# Power.net
KiCad netlist of a schematic drawn in Altium Designer
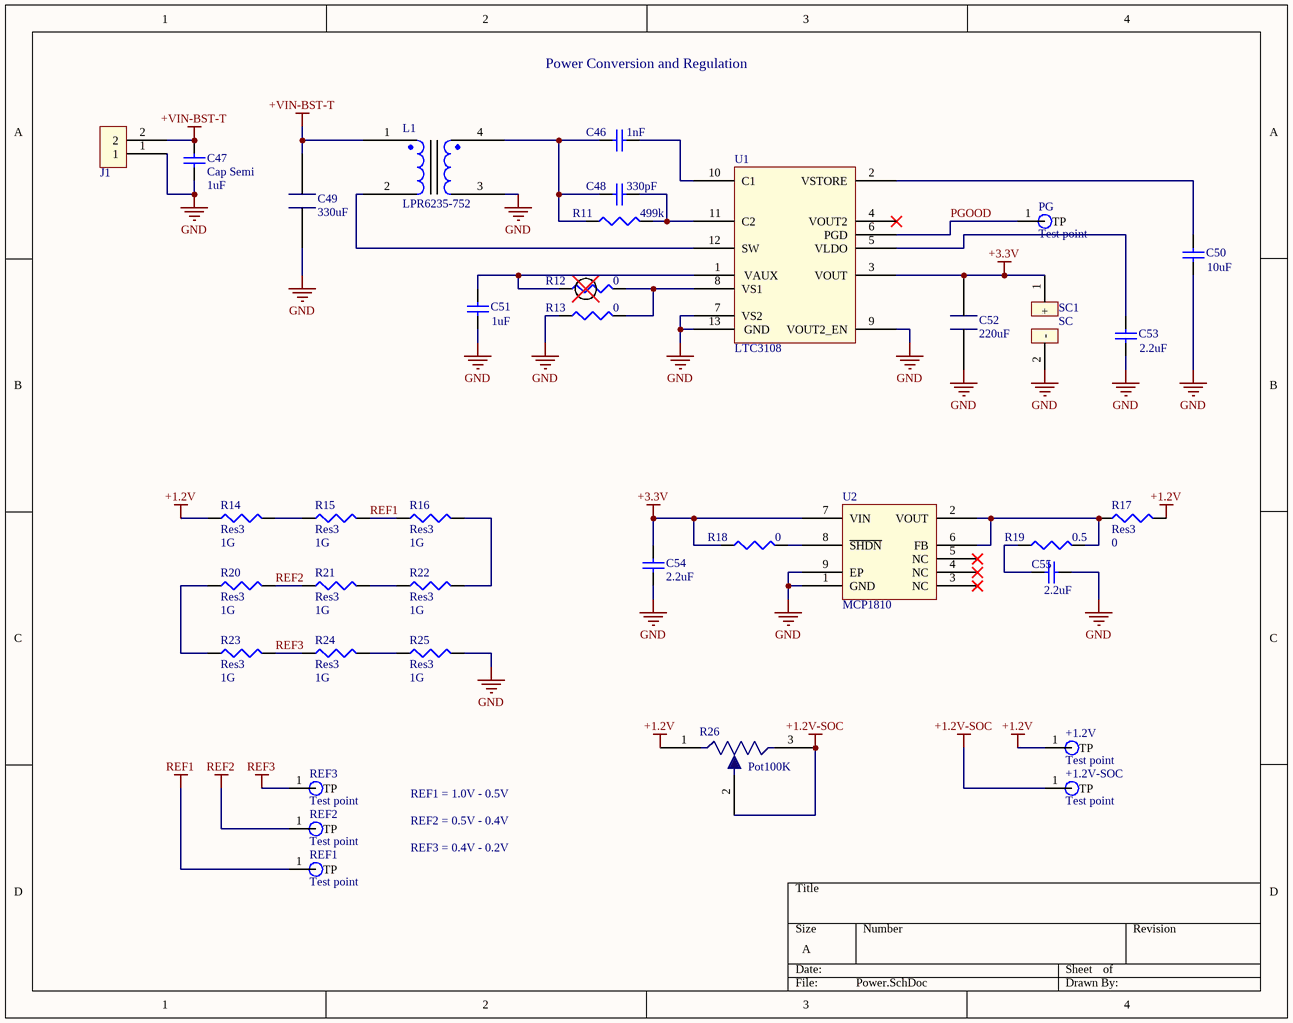
[diagram p0: Power.SchDoc]

(export (version "E")
  (design (tool "Eeschema 10.0.6"))
  (components
    (comp (ref "+1.2V") (value "Test point") (footprint "TP") (libsource (lib "INERTIA") (part "Test point")))
    (comp (ref "+1.2V-SOC")
      (value "Test point")
      (footprint "TP")
      (libsource (lib "INERTIA") (part "Test point"))
    )
    (comp (ref "C46")
      (value "1nF")
      (footprint "0402")
      (description "Capacitor (Semiconductor SIM Model)")
      (fields (field (name "Comment") "Cap Semi") (field (name "PUBLISHER") "Altium Limited"))
      (libsource (lib "Miscellaneous Devices") (part "Cap Semi"))
    )
    (comp (ref "C47")
      (value "Cap Semi")
      (footprint "0402")
      (description "Capacitor (Semiconductor SIM Model)")
      (fields (field (name "ALTIUM_VALUE") "1uF") (field (name "PUBLISHER") "Altium Limited"))
      (libsource (lib "Miscellaneous Devices") (part "Cap Semi"))
    )
    (comp (ref "C48")
      (value "330pF")
      (footprint "0402")
      (description "Capacitor (Semiconductor SIM Model)")
      (fields (field (name "Comment") "Cap Semi") (field (name "PUBLISHER") "Altium Limited"))
      (libsource (lib "Miscellaneous Devices") (part "Cap Semi"))
    )
    (comp (ref "C49")
      (value "330uF")
      (footprint "CAPCP7343X43NEW")
      (libsource (lib "ASSIST") (part "BoostCap"))
    )
    (comp (ref "C50")
      (value "10uF")
      (footprint "0402")
      (description "Capacitor (Semiconductor SIM Model)")
      (fields (field (name "Comment") "Cap Semi") (field (name "PUBLISHER") "Altium Limited"))
      (libsource (lib "Miscellaneous Devices") (part "Cap Semi"))
    )
    (comp (ref "C51")
      (value "1uF")
      (footprint "0402")
      (description "Capacitor (Semiconductor SIM Model)")
      (fields (field (name "Comment") "Cap Semi") (field (name "PUBLISHER") "Altium Limited"))
      (libsource (lib "Miscellaneous Devices") (part "Cap Semi"))
    )
    (comp (ref "C52")
      (value "220uF")
      (footprint "CAPCP7343X43NEW")
      (libsource (lib "ASSIST") (part "BoostCap"))
    )
    (comp (ref "C53")
      (value "2.2uF")
      (footprint "0402")
      (description "Capacitor (Semiconductor SIM Model)")
      (fields (field (name "Comment") "Cap Semi") (field (name "PUBLISHER") "Altium Limited"))
      (libsource (lib "Miscellaneous Devices") (part "Cap Semi"))
    )
    (comp (ref "C54")
      (value "2.2uF")
      (footprint "0402")
      (description "Capacitor (Semiconductor SIM Model)")
      (fields (field (name "Comment") "Cap Semi") (field (name "PUBLISHER") "Altium Limited"))
      (libsource (lib "Miscellaneous Devices") (part "Cap Semi"))
    )
    (comp (ref "C55")
      (value "2.2uF")
      (footprint "0402")
      (description "Capacitor (Semiconductor SIM Model)")
      (fields (field (name "Comment") "Cap Semi") (field (name "PUBLISHER") "Altium Limited"))
      (libsource (lib "Miscellaneous Devices") (part "Cap Semi"))
    )
    (comp (ref "J1")
      (value "MolexPicoLock")
      (footprint "5037630291_MolexPicoLock")
      (description "Molex Pico Lock 2 pin")
      (libsource (lib "INERTIA") (part "MolexPicoLock"))
    )
    (comp (ref "L1")
      (value "LPR6235-752")
      (footprint "LPR6235-752")
      (libsource (lib "INERTIA") (part "LPR6235-752"))
    )
    (comp (ref "PG") (value "Test point") (footprint "TP") (libsource (lib "INERTIA") (part "Test point")))
    (comp (ref "R11")
      (value "499k")
      (footprint "0402")
      (description "Resistor")
      (fields (field (name "Comment") "Res3") (field (name "PUBLISHER") "Altium Limited"))
      (libsource (lib "Miscellaneous Devices") (part "Res3"))
    )
    (comp (ref "R12")
      (value "0")
      (footprint "0402")
      (description "Resistor")
      (fields (field (name "Comment") "Res3") (field (name "PUBLISHER") "Altium Limited"))
      (libsource (lib "Miscellaneous Devices") (part "Res3"))
    )
    (comp (ref "R13")
      (value "0")
      (footprint "0402")
      (description "Resistor")
      (fields (field (name "Comment") "Res3") (field (name "PUBLISHER") "Altium Limited"))
      (libsource (lib "Miscellaneous Devices") (part "Res3"))
    )
    (comp (ref "R14")
      (value "Res3")
      (footprint "6-0805_N")
      (description "Resistor")
      (fields (field (name "ALTIUM_VALUE") "1G") (field (name "PUBLISHER") "Altium Limited"))
      (libsource (lib "Miscellaneous Devices") (part "Res3"))
    )
    (comp (ref "R15")
      (value "Res3")
      (footprint "6-0805_N")
      (description "Resistor")
      (fields (field (name "ALTIUM_VALUE") "1G") (field (name "PUBLISHER") "Altium Limited"))
      (libsource (lib "Miscellaneous Devices") (part "Res3"))
    )
    (comp (ref "R16")
      (value "Res3")
      (footprint "6-0805_N")
      (description "Resistor")
      (fields (field (name "ALTIUM_VALUE") "1G") (field (name "PUBLISHER") "Altium Limited"))
      (libsource (lib "Miscellaneous Devices") (part "Res3"))
    )
    (comp (ref "R17")
      (value "Res3")
      (footprint "0402")
      (description "Resistor")
      (fields (field (name "ALTIUM_VALUE") "0") (field (name "PUBLISHER") "Altium Limited"))
      (libsource (lib "Miscellaneous Devices") (part "Res3"))
    )
    (comp (ref "R18")
      (value "0")
      (footprint "0402")
      (description "Resistor")
      (fields (field (name "Comment") "Res3") (field (name "PUBLISHER") "Altium Limited"))
      (libsource (lib "Miscellaneous Devices") (part "Res3"))
    )
    (comp (ref "R19")
      (value "0.5")
      (footprint "0402")
      (description "Resistor")
      (fields (field (name "Comment") "Res3") (field (name "PUBLISHER") "Altium Limited"))
      (libsource (lib "Miscellaneous Devices") (part "Res3"))
    )
    (comp (ref "R20")
      (value "Res3")
      (footprint "6-0805_N")
      (description "Resistor")
      (fields (field (name "ALTIUM_VALUE") "1G") (field (name "PUBLISHER") "Altium Limited"))
      (libsource (lib "Miscellaneous Devices") (part "Res3"))
    )
    (comp (ref "R21")
      (value "Res3")
      (footprint "6-0805_N")
      (description "Resistor")
      (fields (field (name "ALTIUM_VALUE") "1G") (field (name "PUBLISHER") "Altium Limited"))
      (libsource (lib "Miscellaneous Devices") (part "Res3"))
    )
    (comp (ref "R22")
      (value "Res3")
      (footprint "6-0805_N")
      (description "Resistor")
      (fields (field (name "ALTIUM_VALUE") "1G") (field (name "PUBLISHER") "Altium Limited"))
      (libsource (lib "Miscellaneous Devices") (part "Res3"))
    )
    (comp (ref "R23")
      (value "Res3")
      (footprint "6-0805_N")
      (description "Resistor")
      (fields (field (name "ALTIUM_VALUE") "1G") (field (name "PUBLISHER") "Altium Limited"))
      (libsource (lib "Miscellaneous Devices") (part "Res3"))
    )
    (comp (ref "R24")
      (value "Res3")
      (footprint "6-0805_N")
      (description "Resistor")
      (fields (field (name "ALTIUM_VALUE") "1G") (field (name "PUBLISHER") "Altium Limited"))
      (libsource (lib "Miscellaneous Devices") (part "Res3"))
    )
    (comp (ref "R25")
      (value "Res3")
      (footprint "6-0805_N")
      (description "Resistor")
      (fields (field (name "ALTIUM_VALUE") "1G") (field (name "PUBLISHER") "Altium Limited"))
      (libsource (lib "Miscellaneous Devices") (part "Res3"))
    )
    (comp (ref "R26")
      (value "Pot100K")
      (footprint "Pot100K")
      (description "EVM-2WSX80B15 100K Trimpot SMD")
      (libsource (lib "INERTIA") (part "Pot100K"))
    )
    (comp (ref "REF1") (value "Test point") (footprint "TP") (libsource (lib "INERTIA") (part "Test point")))
    (comp (ref "REF2") (value "Test point") (footprint "TP") (libsource (lib "INERTIA") (part "Test point")))
    (comp (ref "REF3") (value "Test point") (footprint "TP") (libsource (lib "INERTIA") (part "Test point")))
    (comp (ref "SC1")
      (value "SC")
      (footprint "SocketBattCR2032")
      (description "Socket Battery CR2032")
      (libsource (lib "INERTIA") (part "Soket Battery CR2032"))
    )
    (comp (ref "U1")
      (value "LTC3108")
      (footprint "QFN0P300X400X80_HS-13M")
      (libsource (lib "INERTIA") (part "LTC3108"))
    )
    (comp (ref "U2")
      (value "MCP1810")
      (footprint "MCP1810")
      (description "Ultra-low Power LDO")
      (libsource (lib "INERTIA") (part "MCP1810"))
    )
  )
  (nets
    (net (code "1") (name "+1.2V") (class "Default")
      (node (ref "+1.2V") (pin "1") (pinfunction "TP_1") (pintype "passive"))
      (node (ref "R14") (pin "1") (pinfunction "1_1") (pintype "passive"))
      (node (ref "R17") (pin "2") (pinfunction "2_2") (pintype "passive"))
      (node (ref "R26") (pin "1") (pinfunction "1_1") (pintype "passive"))
    )
    (net (code "2") (name "+1.2V-SOC") (class "Default")
      (node (ref "+1.2V-SOC") (pin "1") (pinfunction "TP_1") (pintype "passive"))
      (node (ref "R26") (pin "2") (pinfunction "2_2") (pintype "passive"))
      (node (ref "R26") (pin "3") (pinfunction "3_3") (pintype "passive"))
    )
    (net (code "3") (name "+3.3V") (class "Default")
      (node (ref "C52") (pin "1") (pinfunction "1_1") (pintype "passive"))
      (node (ref "C54") (pin "2") (pinfunction "2_2") (pintype "passive"))
      (node (ref "R18") (pin "1") (pinfunction "1_1") (pintype "passive"))
      (node (ref "SC1") (pin "1") (pinfunction "+_1") (pintype "passive"))
      (node (ref "U1") (pin "3") (pinfunction "VOUT_3") (pintype "passive"))
      (node (ref "U2") (pin "7") (pinfunction "VIN_7") (pintype "passive"))
    )
    (net (code "4") (name "+VIN-BST-T") (class "Default")
      (node (ref "C47") (pin "1") (pinfunction "1_1") (pintype "passive"))
      (node (ref "C49") (pin "1") (pinfunction "1_1") (pintype "passive"))
      (node (ref "J1") (pin "2") (pinfunction "2_2") (pintype "passive"))
      (node (ref "L1") (pin "1") (pinfunction "1_1") (pintype "passive"))
    )
    (net (code "5") (name "/PGOOD") (class "Default")
      (node (ref "PG") (pin "1") (pinfunction "TP_1") (pintype "passive"))
      (node (ref "U1") (pin "6") (pinfunction "PGD_6") (pintype "passive"))
    )
    (net (code "6") (name "GND") (class "Default")
      (node (ref "C47") (pin "2") (pinfunction "2_2") (pintype "passive"))
      (node (ref "C49") (pin "2") (pinfunction "2_2") (pintype "passive"))
      (node (ref "C50") (pin "1") (pinfunction "1_1") (pintype "passive"))
      (node (ref "C51") (pin "1") (pinfunction "1_1") (pintype "passive"))
      (node (ref "C52") (pin "2") (pinfunction "2_2") (pintype "passive"))
      (node (ref "C53") (pin "1") (pinfunction "1_1") (pintype "passive"))
      (node (ref "C54") (pin "1") (pinfunction "1_1") (pintype "passive"))
      (node (ref "C55") (pin "1") (pinfunction "1_1") (pintype "passive"))
      (node (ref "J1") (pin "1") (pinfunction "1_1") (pintype "passive"))
      (node (ref "L1") (pin "3") (pinfunction "3_3") (pintype "passive"))
      (node (ref "R13") (pin "1") (pinfunction "1_1") (pintype "passive"))
      (node (ref "R25") (pin "2") (pinfunction "2_2") (pintype "passive"))
      (node (ref "SC1") (pin "2") (pinfunction "-_2") (pintype "passive"))
      (node (ref "U1") (pin "13") (pinfunction "GND_13") (pintype "passive"))
      (node (ref "U1") (pin "7") (pinfunction "VS2_7") (pintype "passive"))
      (node (ref "U1") (pin "9") (pinfunction "VOUT2_EN_9") (pintype "passive"))
      (node (ref "U2") (pin "1") (pinfunction "GND_1") (pintype "passive"))
      (node (ref "U2") (pin "9") (pinfunction "EP_9") (pintype "passive"))
    )
    (net (code "7") (name "Net-(C46-Pad1)") (class "Default")
      (node (ref "C46") (pin "1") (pinfunction "1_1") (pintype "passive"))
      (node (ref "C48") (pin "1") (pinfunction "1_1") (pintype "passive"))
      (node (ref "L1") (pin "4") (pinfunction "4_4") (pintype "passive"))
      (node (ref "R11") (pin "1") (pinfunction "1_1") (pintype "passive"))
    )
    (net (code "8") (name "Net-(C55-Pad2)") (class "Default")
      (node (ref "C55") (pin "2") (pinfunction "2_2") (pintype "passive"))
      (node (ref "R19") (pin "1") (pinfunction "1_1") (pintype "passive"))
    )
    (net (code "9") (name "Net-(R14-Pad2)") (class "Default")
      (node (ref "R14") (pin "2") (pinfunction "2_2") (pintype "passive"))
      (node (ref "R15") (pin "1") (pinfunction "1_1") (pintype "passive"))
    )
    (net (code "10") (name "Net-(R16-Pad2)") (class "Default")
      (node (ref "R16") (pin "2") (pinfunction "2_2") (pintype "passive"))
      (node (ref "R22") (pin "2") (pinfunction "2_2") (pintype "passive"))
    )
    (net (code "11") (name "Net-(R20-Pad1)") (class "Default")
      (node (ref "R20") (pin "1") (pinfunction "1_1") (pintype "passive"))
      (node (ref "R23") (pin "1") (pinfunction "1_1") (pintype "passive"))
    )
    (net (code "12") (name "Net-(R21-Pad2)") (class "Default")
      (node (ref "R21") (pin "2") (pinfunction "2_2") (pintype "passive"))
      (node (ref "R22") (pin "1") (pinfunction "1_1") (pintype "passive"))
    )
    (net (code "13") (name "Net-(R24-Pad2)") (class "Default")
      (node (ref "R24") (pin "2") (pinfunction "2_2") (pintype "passive"))
      (node (ref "R25") (pin "1") (pinfunction "1_1") (pintype "passive"))
    )
    (net (code "14") (name "Net-(U1-C1)") (class "Default")
      (node (ref "C46") (pin "2") (pinfunction "2_2") (pintype "passive"))
      (node (ref "U1") (pin "10") (pinfunction "C1_10") (pintype "passive"))
    )
    (net (code "15") (name "Net-(U1-C2)") (class "Default")
      (node (ref "C48") (pin "2") (pinfunction "2_2") (pintype "passive"))
      (node (ref "R11") (pin "2") (pinfunction "2_2") (pintype "passive"))
      (node (ref "U1") (pin "11") (pinfunction "C2_11") (pintype "passive"))
    )
    (net (code "16") (name "Net-(U1-SW)") (class "Default")
      (node (ref "L1") (pin "2") (pinfunction "2_2") (pintype "passive"))
      (node (ref "U1") (pin "12") (pinfunction "SW_12") (pintype "passive"))
    )
    (net (code "17") (name "Net-(U1-VAUX)") (class "Default")
      (node (ref "C51") (pin "2") (pinfunction "2_2") (pintype "passive"))
      (node (ref "R12") (pin "1") (pinfunction "1_1") (pintype "passive"))
      (node (ref "U1") (pin "1") (pinfunction "VAUX_1") (pintype "passive"))
    )
    (net (code "18") (name "Net-(U1-VLDO)") (class "Default")
      (node (ref "C53") (pin "2") (pinfunction "2_2") (pintype "passive"))
      (node (ref "U1") (pin "5") (pinfunction "VLDO_5") (pintype "passive"))
    )
    (net (code "19") (name "Net-(U1-VS1)") (class "Default")
      (node (ref "R12") (pin "2") (pinfunction "2_2") (pintype "passive"))
      (node (ref "R13") (pin "2") (pinfunction "2_2") (pintype "passive"))
      (node (ref "U1") (pin "8") (pinfunction "VS1_8") (pintype "passive"))
    )
    (net (code "20") (name "Net-(U1-VSTORE)") (class "Default")
      (node (ref "C50") (pin "2") (pinfunction "2_2") (pintype "passive"))
      (node (ref "U1") (pin "2") (pinfunction "VSTORE_2") (pintype "passive"))
    )
    (net (code "21") (name "Net-(U2-FB)") (class "Default")
      (node (ref "R17") (pin "1") (pinfunction "1_1") (pintype "passive"))
      (node (ref "R19") (pin "2") (pinfunction "2_2") (pintype "passive"))
      (node (ref "U2") (pin "2") (pinfunction "VOUT_2") (pintype "passive"))
      (node (ref "U2") (pin "6") (pinfunction "FB_6") (pintype "passive"))
    )
    (net (code "22") (name "Net-(U2-~{SHDN})") (class "Default")
      (node (ref "R18") (pin "2") (pinfunction "2_2") (pintype "passive"))
      (node (ref "U2") (pin "8") (pinfunction "~{SHDN}_8") (pintype "passive"))
    )
    (net (code "23") (name "REF1") (class "Default")
      (node (ref "R15") (pin "2") (pinfunction "2_2") (pintype "passive"))
      (node (ref "R16") (pin "1") (pinfunction "1_1") (pintype "passive"))
      (node (ref "REF1") (pin "1") (pinfunction "TP_1") (pintype "passive"))
    )
    (net (code "24") (name "REF2") (class "Default")
      (node (ref "R20") (pin "2") (pinfunction "2_2") (pintype "passive"))
      (node (ref "R21") (pin "1") (pinfunction "1_1") (pintype "passive"))
      (node (ref "REF2") (pin "1") (pinfunction "TP_1") (pintype "passive"))
    )
    (net (code "25") (name "REF3") (class "Default")
      (node (ref "R23") (pin "2") (pinfunction "2_2") (pintype "passive"))
      (node (ref "R24") (pin "1") (pinfunction "1_1") (pintype "passive"))
      (node (ref "REF3") (pin "1") (pinfunction "TP_1") (pintype "passive"))
    )
    (net (code "26") (name "unconnected-(U1-VOUT2-Pad4)") (class "Default")
      (node (ref "U1") (pin "4") (pinfunction "VOUT2_4") (pintype "passive+no_connect"))
    )
    (net (code "27") (name "unconnected-(U2-NC-Pad3)") (class "Default")
      (node (ref "U2") (pin "3") (pinfunction "NC_3") (pintype "passive+no_connect"))
    )
    (net (code "28") (name "unconnected-(U2-NC-Pad4)") (class "Default")
      (node (ref "U2") (pin "4") (pinfunction "NC_4") (pintype "passive+no_connect"))
    )
    (net (code "29") (name "unconnected-(U2-NC-Pad5)") (class "Default")
      (node (ref "U2") (pin "5") (pinfunction "NC_5") (pintype "passive+no_connect"))
    )
  )
)
